# Sheet1.net
KiCad netlist of a schematic drawn in Altium Designer
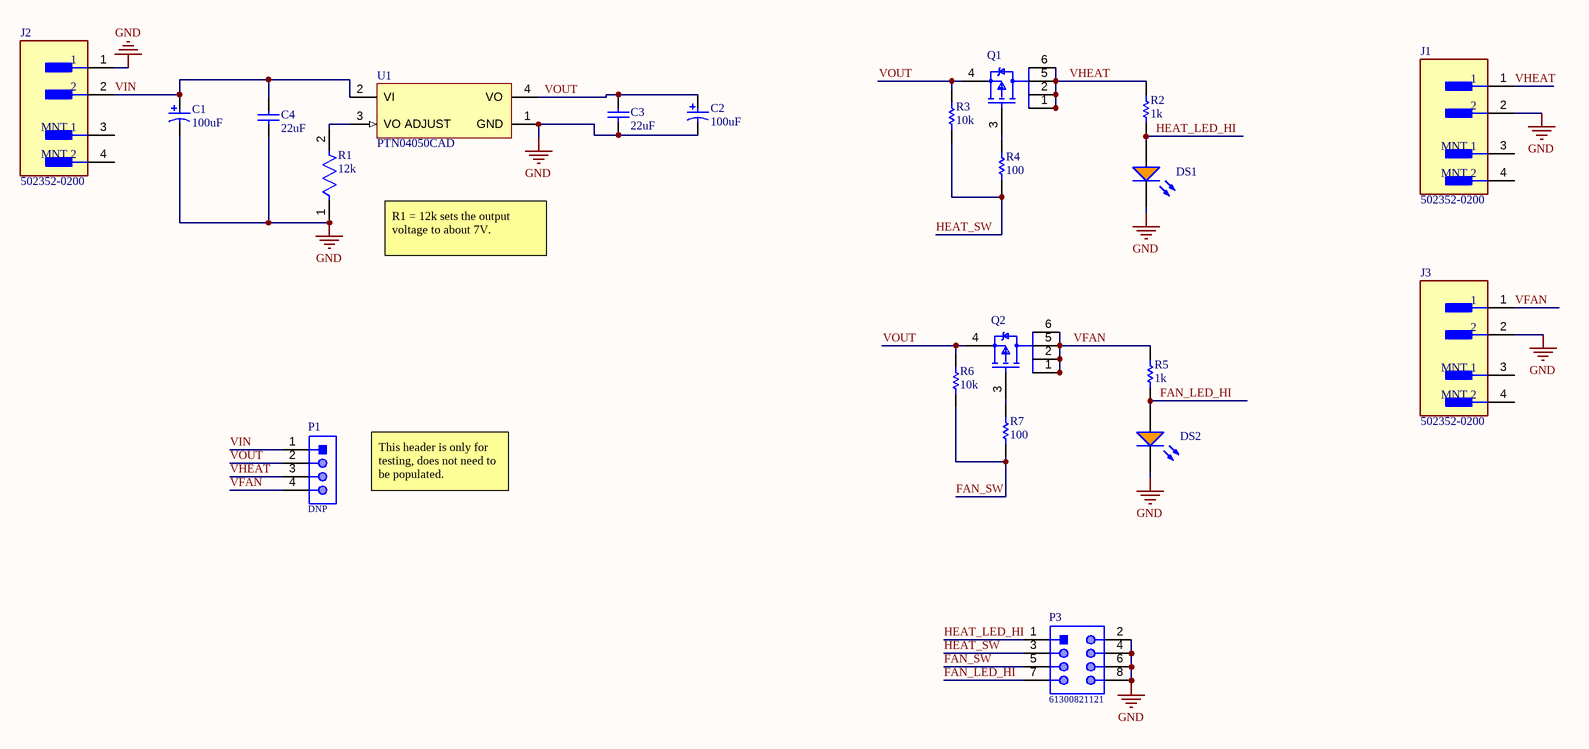
[diagram p0: Sheet1.SchDoc]

(export (version "E")
  (design (tool "Eeschema 10.0.6"))
  (components
    (comp (ref "C1")
      (value "100uF")
      (footprint "PNSC-FK-V-D8_V")
      (fields (field (name "MANUFACTURER") "Panasonic"))
      (libsource (lib "Altium Content Vault") (part "CAP-P-2"))
    )
    (comp (ref "C2")
      (value "100uF")
      (footprint "PNSC-FK-V-D8_V")
      (fields (field (name "MANUFACTURER") "Panasonic"))
      (libsource (lib "Altium Content Vault") (part "CAP-P-2"))
    )
    (comp (ref "C3")
      (value "22uF")
      (footprint "MURA-1210_H_2.7_L")
      (fields (field (name "MANUFACTURER") "Murata") (field (name "TOLERANCE") "±10%"))
      (libsource (lib "Altium Content Vault") (part "CAP-NP-2"))
    )
    (comp (ref "C4")
      (value "22uF")
      (footprint "MURA-1210_H_2.7_L")
      (fields (field (name "MANUFACTURER") "Murata") (field (name "TOLERANCE") "±10%"))
      (libsource (lib "Altium Content Vault") (part "CAP-NP-2"))
    )
    (comp (ref "DS1")
      (value "HSMD-C170")
      (footprint "AVAG-HSMX-C170_V")
      (description "LED Uni-Color Orange, 52 mW, 20 mA, -40 to 85 degC, 2-Pin SMD, RoHS, Tape and Reel")
      (fields (field (name "MANUFACTURER") "Avago"))
      (libsource (lib "Altium Content Vault") (part "LED-ORANGE-AK-2"))
    )
    (comp (ref "DS2")
      (value "HSMD-C170")
      (footprint "AVAG-HSMX-C170_V")
      (description "LED Uni-Color Orange, 52 mW, 20 mA, -40 to 85 degC, 2-Pin SMD, RoHS, Tape and Reel")
      (fields (field (name "MANUFACTURER") "Avago"))
      (libsource (lib "Altium Content Vault") (part "LED-ORANGE-AK-2"))
    )
    (comp (ref "J1")
      (value "502352-0200")
      (footprint "FP-502352-0200-MFG")
      (description "CONN HEADER SMD R/A 2POS 2MM")
      (fields
        (field (name "MANUFACTURER") "Molex")
        (field (name "OCTOPART") "https://octopart.com/502352-0200-molex-9519058")
      )
      (libsource (lib "Altium Content Vault") (part "029478cb6d4f2fad0cd2a245525ee6d"))
    )
    (comp (ref "J2")
      (value "502352-0200")
      (footprint "FP-502352-0200-MFG")
      (description "CONN HEADER SMD R/A 2POS 2MM")
      (fields
        (field (name "MANUFACTURER") "Molex")
        (field (name "OCTOPART") "https://octopart.com/502352-0200-molex-9519058")
      )
      (libsource (lib "Altium Content Vault") (part "029478cb6d4f2fad0cd2a245525ee6d"))
    )
    (comp (ref "J3")
      (value "502352-0200")
      (footprint "FP-502352-0200-MFG")
      (description "CONN HEADER SMD R/A 2POS 2MM")
      (fields
        (field (name "MANUFACTURER") "Molex")
        (field (name "OCTOPART") "https://octopart.com/502352-0200-molex-9519058")
      )
      (libsource (lib "Altium Content Vault") (part "029478cb6d4f2fad0cd2a245525ee6d"))
    )
    (comp (ref "P1")
      (value "DNP")
      (footprint "61300411121")
      (description "THT Vertical Pin Header WR-PHD, Pitch 2.54 mm, Single Row, 4 pins")
      (fields
        (field (name "MANUFACTURER") "Wurth Elektronik")
        (field (name "PART NUMBER") "61300411121")
        (field (name "PUBLISHER") "WurthElektronik")
      )
      (libsource (lib "Altium Content Vault") (part "WE-CN-1P-M-R4"))
    )
    (comp (ref "P3")
      (value "61300821121")
      (footprint "61300821121")
      (description "THT Vertical Pin Header WR-PHD, Pitch 2.54 mm, Dual Row, 8 pins")
      (fields (field (name "MANUFACTURER") "Wurth Elektronik") (field (name "PUBLISHER") "WurthElektronik"))
      (libsource (lib "Altium Content Vault") (part "WE-CN-2P-M-R8"))
    )
    (comp (ref "Q1")
      (value "SI3493DDV-T1-GE3")
      (footprint "FP-C-06593-MFG")
      (description "MOSFET P-CHANNEL 20V 8A 6TSOP")
      (fields
        (field (name "MANUFACTURER") "Vishay")
        (field (name "OCTOPART") "https://octopart.com/si3493ddv-t1-ge3-vishay-81014282")
      )
      (libsource (lib "Altium Content Vault") (part "cb80e2443ef6eac25cf60ecf9c1abdf"))
    )
    (comp (ref "Q2")
      (value "SI3493DDV-T1-GE3")
      (footprint "FP-C-06593-MFG")
      (description "MOSFET P-CHANNEL 20V 8A 6TSOP")
      (fields
        (field (name "MANUFACTURER") "Vishay")
        (field (name "OCTOPART") "https://octopart.com/si3493ddv-t1-ge3-vishay-81014282")
      )
      (libsource (lib "Altium Content Vault") (part "cb80e2443ef6eac25cf60ecf9c1abdf"))
    )
    (comp (ref "R1")
      (value "12k")
      (footprint "FP-CRCW0805-e3-IPC_A")
      (description "RES Thick Film, 12kΩ, 1%, 0.125W, 100ppm/°C, 0805")
      (fields (field (name "TOLERANCE") "1%"))
      (libsource (lib "Altium Content Vault") (part "1029c3af85768c4190bb7ad29bc67b5"))
    )
    (comp (ref "R2")
      (value "1k")
      (footprint "RESC2013X55X40LL15T20")
      (description "TNPW08051K00BEEN")
      (fields (field (name "MANUFACTURER") "Vishay Dale"))
      (libsource (lib "Altium Content Vault") (part "RES"))
    )
    (comp (ref "R3")
      (value "10k")
      (footprint "RESC2013X60X35NL10T20")
      (description "Chip Resistor, 10 KOhm, +/- 1%, 0.125 W, -55 to 155 degC, 0805 (2012 Metric), RoHS, Tape and Reel")
      (fields (field (name "MANUFACTURER") "Yageo"))
      (libsource (lib "Altium Content Vault") (part "RES-2"))
    )
    (comp (ref "R4")
      (value "100")
      (footprint "RESC2013X50X30LL20T20")
      (fields (field (name "MANUFACTURER") "Vishay Dale") (field (name "PART NUMBER") "CRCW0805100RFKEA"))
      (libsource (lib "Altium Content Vault") (part "RES"))
    )
    (comp (ref "R5")
      (value "1k")
      (footprint "RESC2013X55X40LL15T20")
      (description "TNPW08051K00BEEN")
      (fields (field (name "MANUFACTURER") "Vishay Dale"))
      (libsource (lib "Altium Content Vault") (part "RES"))
    )
    (comp (ref "R6")
      (value "10k")
      (footprint "RESC2013X60X35NL10T20")
      (description "Chip Resistor, 10 KOhm, +/- 1%, 0.125 W, -55 to 155 degC, 0805 (2012 Metric), RoHS, Tape and Reel")
      (fields (field (name "MANUFACTURER") "Yageo"))
      (libsource (lib "Altium Content Vault") (part "RES-2"))
    )
    (comp (ref "R7")
      (value "100")
      (footprint "RESC2013X50X30LL20T20")
      (fields (field (name "MANUFACTURER") "Vishay Dale") (field (name "PART NUMBER") "CRCW0805100RFKEA"))
      (libsource (lib "Altium Content Vault") (part "RES"))
    )
    (comp (ref "U1")
      (value "PTN04050CAD")
      (footprint "EUU0004A")
      (fields (field (name "MANUFACTURER") "Texas Instruments"))
      (libsource (lib "Altium Content Vault") (part "TI-PTN04050CEUX4"))
    )
  )
  (nets
    (net (code "1") (name "/FAN_LED_HI") (class "Default")
      (node (ref "DS2") (pin "1") (pinfunction "A_1") (pintype "passive"))
      (node (ref "P3") (pin "7") (pinfunction "7_7") (pintype "passive"))
      (node (ref "R5") (pin "1") (pinfunction "1_1") (pintype "passive"))
    )
    (net (code "2") (name "/FAN_SW") (class "Default")
      (node (ref "P3") (pin "5") (pinfunction "5_5") (pintype "passive"))
      (node (ref "R6") (pin "2") (pinfunction "2_2") (pintype "passive"))
      (node (ref "R7") (pin "1") (pinfunction "1_1") (pintype "passive"))
    )
    (net (code "3") (name "/HEAT_LED_HI") (class "Default")
      (node (ref "DS1") (pin "1") (pinfunction "A_1") (pintype "passive"))
      (node (ref "P3") (pin "1") (pinfunction "1_1") (pintype "passive"))
      (node (ref "R2") (pin "1") (pinfunction "1_1") (pintype "passive"))
    )
    (net (code "4") (name "/HEAT_SW") (class "Default")
      (node (ref "P3") (pin "3") (pinfunction "3_3") (pintype "passive"))
      (node (ref "R3") (pin "2") (pinfunction "2_2") (pintype "passive"))
      (node (ref "R4") (pin "1") (pinfunction "1_1") (pintype "passive"))
    )
    (net (code "5") (name "/VFAN") (class "Default")
      (node (ref "J3") (pin "1") (pinfunction "1_1") (pintype "passive"))
      (node (ref "P1") (pin "4") (pinfunction "4_4") (pintype "passive"))
      (node (ref "Q2") (pin "1") (pinfunction "D_1") (pintype "passive"))
      (node (ref "Q2") (pin "2") (pinfunction "D_2") (pintype "passive"))
      (node (ref "Q2") (pin "5") (pinfunction "D_5") (pintype "passive"))
      (node (ref "Q2") (pin "6") (pinfunction "D_6") (pintype "passive"))
      (node (ref "R5") (pin "2") (pinfunction "2_2") (pintype "passive"))
    )
    (net (code "6") (name "/VHEAT") (class "Default")
      (node (ref "J1") (pin "1") (pinfunction "1_1") (pintype "passive"))
      (node (ref "P1") (pin "3") (pinfunction "3_3") (pintype "passive"))
      (node (ref "Q1") (pin "1") (pinfunction "D_1") (pintype "passive"))
      (node (ref "Q1") (pin "2") (pinfunction "D_2") (pintype "passive"))
      (node (ref "Q1") (pin "5") (pinfunction "D_5") (pintype "passive"))
      (node (ref "Q1") (pin "6") (pinfunction "D_6") (pintype "passive"))
      (node (ref "R2") (pin "2") (pinfunction "2_2") (pintype "passive"))
    )
    (net (code "7") (name "/VIN") (class "Default")
      (node (ref "C1") (pin "1") (pinfunction "1_1") (pintype "passive"))
      (node (ref "C4") (pin "1") (pinfunction "1_1") (pintype "passive"))
      (node (ref "J2") (pin "2") (pinfunction "2_2") (pintype "passive"))
      (node (ref "P1") (pin "1") (pinfunction "1_1") (pintype "passive"))
      (node (ref "U1") (pin "2") (pinfunction "VI_2") (pintype "power_in"))
    )
    (net (code "8") (name "/VOUT") (class "Default")
      (node (ref "C2") (pin "1") (pinfunction "1_1") (pintype "passive"))
      (node (ref "C3") (pin "2") (pinfunction "2_2") (pintype "passive"))
      (node (ref "P1") (pin "2") (pinfunction "2_2") (pintype "passive"))
      (node (ref "Q1") (pin "4") (pinfunction "S_4") (pintype "passive"))
      (node (ref "Q2") (pin "4") (pinfunction "S_4") (pintype "passive"))
      (node (ref "R3") (pin "1") (pinfunction "1_1") (pintype "passive"))
      (node (ref "R6") (pin "1") (pinfunction "1_1") (pintype "passive"))
      (node (ref "U1") (pin "4") (pinfunction "VO_4") (pintype "power_in"))
    )
    (net (code "9") (name "GND") (class "Default")
      (node (ref "C1") (pin "2") (pinfunction "2_2") (pintype "passive"))
      (node (ref "C2") (pin "2") (pinfunction "2_2") (pintype "passive"))
      (node (ref "C3") (pin "1") (pinfunction "1_1") (pintype "passive"))
      (node (ref "C4") (pin "2") (pinfunction "2_2") (pintype "passive"))
      (node (ref "DS1") (pin "2") (pinfunction "K_2") (pintype "passive"))
      (node (ref "DS2") (pin "2") (pinfunction "K_2") (pintype "passive"))
      (node (ref "J1") (pin "2") (pinfunction "2_2") (pintype "passive"))
      (node (ref "J2") (pin "1") (pinfunction "1_1") (pintype "passive"))
      (node (ref "J3") (pin "2") (pinfunction "2_2") (pintype "passive"))
      (node (ref "P3") (pin "2") (pinfunction "2_2") (pintype "passive"))
      (node (ref "P3") (pin "4") (pinfunction "4_4") (pintype "passive"))
      (node (ref "P3") (pin "6") (pinfunction "6_6") (pintype "passive"))
      (node (ref "P3") (pin "8") (pinfunction "8_8") (pintype "passive"))
      (node (ref "R1") (pin "1") (pinfunction "1_1") (pintype "passive"))
      (node (ref "U1") (pin "1") (pinfunction "GND_1") (pintype "power_in"))
    )
    (net (code "10") (name "Net-(Q1-G)") (class "Default")
      (node (ref "Q1") (pin "3") (pinfunction "G_3") (pintype "passive"))
      (node (ref "R4") (pin "2") (pinfunction "2_2") (pintype "passive"))
    )
    (net (code "11") (name "Net-(Q2-G)") (class "Default")
      (node (ref "Q2") (pin "3") (pinfunction "G_3") (pintype "passive"))
      (node (ref "R7") (pin "2") (pinfunction "2_2") (pintype "passive"))
    )
    (net (code "12") (name "Net-(U1-VO_ADJUST)") (class "Default")
      (node (ref "R1") (pin "2") (pinfunction "2_2") (pintype "passive"))
      (node (ref "U1") (pin "3") (pinfunction "VO_ADJUST_3") (pintype "input"))
    )
    (net (code "13") (name "unconnected-(J1-MNT_1-Pad3)") (class "Default")
      (node (ref "J1") (pin "3") (pinfunction "MNT_1_3") (pintype "passive"))
    )
    (net (code "14") (name "unconnected-(J1-MNT_2-Pad4)") (class "Default")
      (node (ref "J1") (pin "4") (pinfunction "MNT_2_4") (pintype "passive"))
    )
    (net (code "15") (name "unconnected-(J2-MNT_1-Pad3)") (class "Default")
      (node (ref "J2") (pin "3") (pinfunction "MNT_1_3") (pintype "passive"))
    )
    (net (code "16") (name "unconnected-(J2-MNT_2-Pad4)") (class "Default")
      (node (ref "J2") (pin "4") (pinfunction "MNT_2_4") (pintype "passive"))
    )
    (net (code "17") (name "unconnected-(J3-MNT_1-Pad3)") (class "Default")
      (node (ref "J3") (pin "3") (pinfunction "MNT_1_3") (pintype "passive"))
    )
    (net (code "18") (name "unconnected-(J3-MNT_2-Pad4)") (class "Default")
      (node (ref "J3") (pin "4") (pinfunction "MNT_2_4") (pintype "passive"))
    )
  )
)
